# air.net
KiCad netlist of a schematic drawn in EAGLE
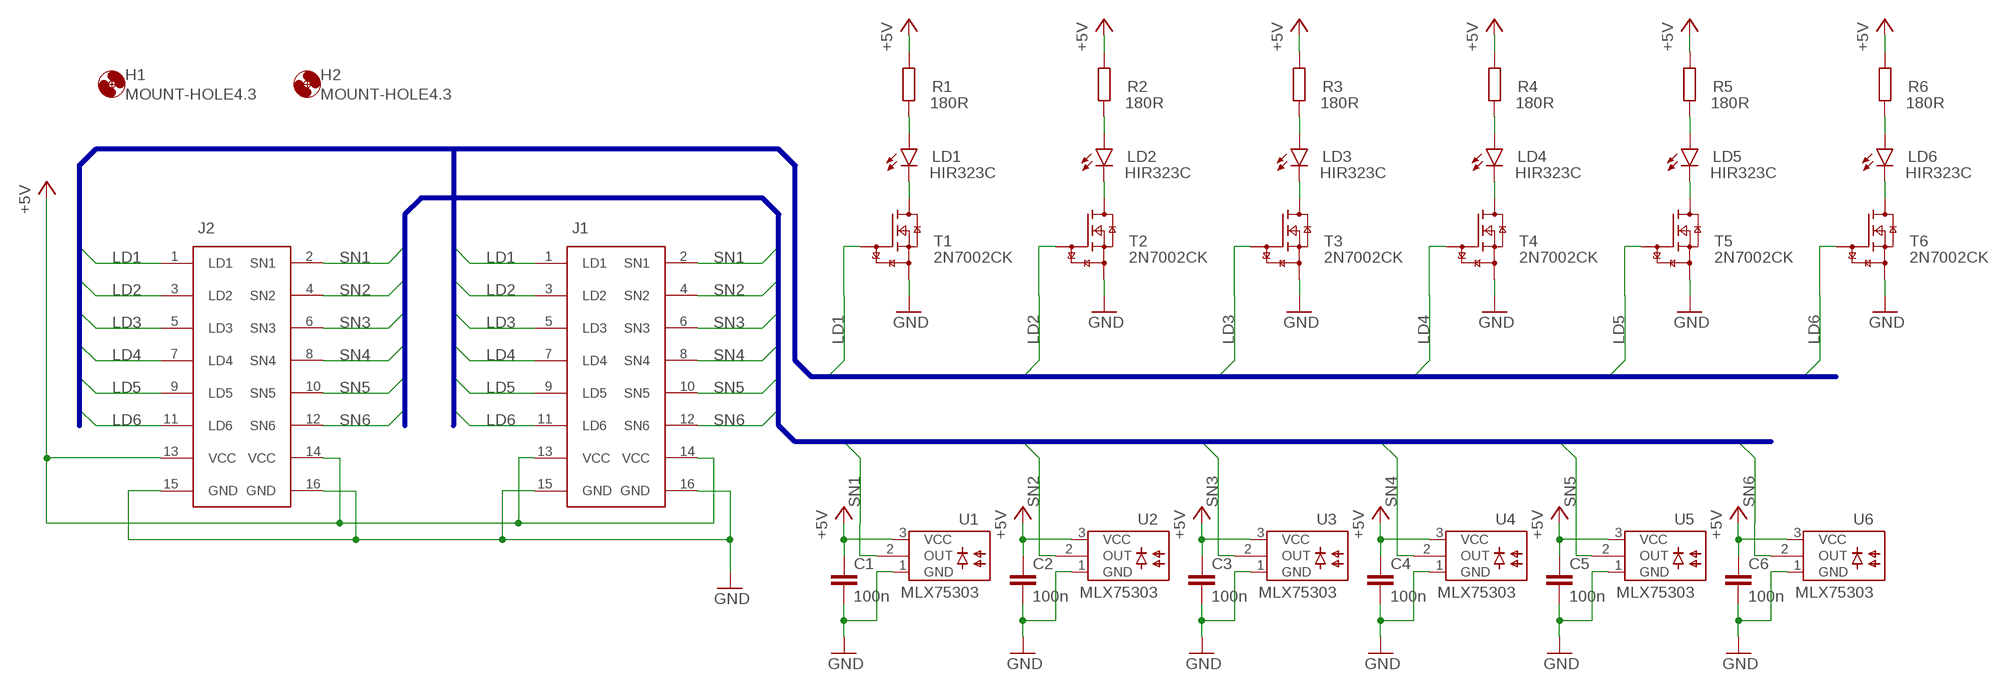
[diagram p0: schematic, sheet 1]

(export (version "E")
  (design (tool "Eeschema 10.0.6"))
  (components
    (comp (ref "C1")
      (value "100n")
      (footprint "eagle-import:C0805K")
      (libsource (lib "eagle-import") (part "C-EUC0805K"))
    )
    (comp (ref "C2")
      (value "100n")
      (footprint "eagle-import:C0805K")
      (libsource (lib "eagle-import") (part "C-EUC0805K"))
    )
    (comp (ref "C3")
      (value "100n")
      (footprint "eagle-import:C0805K")
      (libsource (lib "eagle-import") (part "C-EUC0805K"))
    )
    (comp (ref "C4")
      (value "100n")
      (footprint "eagle-import:C0805K")
      (libsource (lib "eagle-import") (part "C-EUC0805K"))
    )
    (comp (ref "C5")
      (value "100n")
      (footprint "eagle-import:C0805K")
      (libsource (lib "eagle-import") (part "C-EUC0805K"))
    )
    (comp (ref "C6")
      (value "100n")
      (footprint "eagle-import:C0805K")
      (libsource (lib "eagle-import") (part "C-EUC0805K"))
    )
    (comp (ref "H1")
      (value "MOUNT-HOLE4.3")
      (footprint "eagle-import:4,3")
      (libsource (lib "eagle-import") (part "MOUNT-HOLE4.3"))
    )
    (comp (ref "H2")
      (value "MOUNT-HOLE4.3")
      (footprint "eagle-import:4,3")
      (libsource (lib "eagle-import") (part "MOUNT-HOLE4.3"))
    )
    (comp (ref "J1")
      (value "2516-SMD-AIR")
      (footprint "eagle-import:612X1620621")
      (libsource (lib "eagle-import") (part "2516-SMD-AIR"))
    )
    (comp (ref "J2")
      (value "2516-SMD-AIR")
      (footprint "eagle-import:612X1620621")
      (libsource (lib "eagle-import") (part "2516-SMD-AIR"))
    )
    (comp (ref "LD1")
      (value "HIR323C")
      (footprint "eagle-import:LEDRD254W60D590H600B")
      (libsource (lib "eagle-import") (part "HIR323C"))
    )
    (comp (ref "LD2")
      (value "HIR323C")
      (footprint "eagle-import:LEDRD254W60D590H600B")
      (libsource (lib "eagle-import") (part "HIR323C"))
    )
    (comp (ref "LD3")
      (value "HIR323C")
      (footprint "eagle-import:LEDRD254W60D590H600B")
      (libsource (lib "eagle-import") (part "HIR323C"))
    )
    (comp (ref "LD4")
      (value "HIR323C")
      (footprint "eagle-import:LEDRD254W60D590H600B")
      (libsource (lib "eagle-import") (part "HIR323C"))
    )
    (comp (ref "LD5")
      (value "HIR323C")
      (footprint "eagle-import:LEDRD254W60D590H600B")
      (libsource (lib "eagle-import") (part "HIR323C"))
    )
    (comp (ref "LD6")
      (value "HIR323C")
      (footprint "eagle-import:LEDRD254W60D590H600B")
      (libsource (lib "eagle-import") (part "HIR323C"))
    )
    (comp (ref "R1")
      (value "180R")
      (footprint "eagle-import:R0805")
      (libsource (lib "eagle-import") (part "R-EU_R0805"))
    )
    (comp (ref "R2")
      (value "180R")
      (footprint "eagle-import:R0805")
      (libsource (lib "eagle-import") (part "R-EU_R0805"))
    )
    (comp (ref "R3")
      (value "180R")
      (footprint "eagle-import:R0805")
      (libsource (lib "eagle-import") (part "R-EU_R0805"))
    )
    (comp (ref "R4")
      (value "180R")
      (footprint "eagle-import:R0805")
      (libsource (lib "eagle-import") (part "R-EU_R0805"))
    )
    (comp (ref "R5")
      (value "180R")
      (footprint "eagle-import:R0805")
      (libsource (lib "eagle-import") (part "R-EU_R0805"))
    )
    (comp (ref "R6")
      (value "180R")
      (footprint "eagle-import:R0805")
      (libsource (lib "eagle-import") (part "R-EU_R0805"))
    )
    (comp (ref "T1")
      (value "2N7002CK")
      (footprint "eagle-import:SOT23")
      (libsource (lib "eagle-import") (part "2N7002CK"))
    )
    (comp (ref "T2")
      (value "2N7002CK")
      (footprint "eagle-import:SOT23")
      (libsource (lib "eagle-import") (part "2N7002CK"))
    )
    (comp (ref "T3")
      (value "2N7002CK")
      (footprint "eagle-import:SOT23")
      (libsource (lib "eagle-import") (part "2N7002CK"))
    )
    (comp (ref "T4")
      (value "2N7002CK")
      (footprint "eagle-import:SOT23")
      (libsource (lib "eagle-import") (part "2N7002CK"))
    )
    (comp (ref "T5")
      (value "2N7002CK")
      (footprint "eagle-import:SOT23")
      (libsource (lib "eagle-import") (part "2N7002CK"))
    )
    (comp (ref "T6")
      (value "2N7002CK")
      (footprint "eagle-import:SOT23")
      (libsource (lib "eagle-import") (part "2N7002CK"))
    )
    (comp (ref "U1")
      (value "MLX75303")
      (footprint "eagle-import:SOIC127P600X147-8N")
      (libsource (lib "eagle-import") (part "MLX75303"))
    )
    (comp (ref "U2")
      (value "MLX75303")
      (footprint "eagle-import:SOIC127P600X147-8N")
      (libsource (lib "eagle-import") (part "MLX75303"))
    )
    (comp (ref "U3")
      (value "MLX75303")
      (footprint "eagle-import:SOIC127P600X147-8N")
      (libsource (lib "eagle-import") (part "MLX75303"))
    )
    (comp (ref "U4")
      (value "MLX75303")
      (footprint "eagle-import:SOIC127P600X147-8N")
      (libsource (lib "eagle-import") (part "MLX75303"))
    )
    (comp (ref "U5")
      (value "MLX75303")
      (footprint "eagle-import:SOIC127P600X147-8N")
      (libsource (lib "eagle-import") (part "MLX75303"))
    )
    (comp (ref "U6")
      (value "MLX75303")
      (footprint "eagle-import:SOIC127P600X147-8N")
      (libsource (lib "eagle-import") (part "MLX75303"))
    )
  )
  (nets
    (net (code "1") (name "+5V") (class "Default")
      (node (ref "C1") (pin "1") (pinfunction "1_1") (pintype "passive"))
      (node (ref "C2") (pin "1") (pinfunction "1_1") (pintype "passive"))
      (node (ref "C3") (pin "1") (pinfunction "1_1") (pintype "passive"))
      (node (ref "C4") (pin "1") (pinfunction "1_1") (pintype "passive"))
      (node (ref "C5") (pin "1") (pinfunction "1_1") (pintype "passive"))
      (node (ref "C6") (pin "1") (pinfunction "1_1") (pintype "passive"))
      (node (ref "J1") (pin "13") (pinfunction "VCC_13") (pintype "passive"))
      (node (ref "J1") (pin "14") (pinfunction "VCC_14") (pintype "passive"))
      (node (ref "J2") (pin "13") (pinfunction "VCC_13") (pintype "passive"))
      (node (ref "J2") (pin "14") (pinfunction "VCC_14") (pintype "passive"))
      (node (ref "R1") (pin "2") (pinfunction "2_2") (pintype "passive"))
      (node (ref "R2") (pin "2") (pinfunction "2_2") (pintype "passive"))
      (node (ref "R3") (pin "2") (pinfunction "2_2") (pintype "passive"))
      (node (ref "R4") (pin "2") (pinfunction "2_2") (pintype "passive"))
      (node (ref "R5") (pin "2") (pinfunction "2_2") (pintype "passive"))
      (node (ref "R6") (pin "2") (pinfunction "2_2") (pintype "passive"))
      (node (ref "U1") (pin "3") (pinfunction "VCC_3") (pintype "power_in"))
      (node (ref "U2") (pin "3") (pinfunction "VCC_3") (pintype "power_in"))
      (node (ref "U3") (pin "3") (pinfunction "VCC_3") (pintype "power_in"))
      (node (ref "U4") (pin "3") (pinfunction "VCC_3") (pintype "power_in"))
      (node (ref "U5") (pin "3") (pinfunction "VCC_3") (pintype "power_in"))
      (node (ref "U6") (pin "3") (pinfunction "VCC_3") (pintype "power_in"))
    )
    (net (code "2") (name "/LD1") (class "Default")
      (node (ref "J1") (pin "1") (pinfunction "LD1_1") (pintype "passive"))
      (node (ref "J2") (pin "1") (pinfunction "LD1_1") (pintype "passive"))
      (node (ref "T1") (pin "1") (pinfunction "G_1") (pintype "passive"))
    )
    (net (code "3") (name "/LD2") (class "Default")
      (node (ref "J1") (pin "3") (pinfunction "LD2_3") (pintype "passive"))
      (node (ref "J2") (pin "3") (pinfunction "LD2_3") (pintype "passive"))
      (node (ref "T2") (pin "1") (pinfunction "G_1") (pintype "passive"))
    )
    (net (code "4") (name "/LD3") (class "Default")
      (node (ref "J1") (pin "5") (pinfunction "LD3_5") (pintype "passive"))
      (node (ref "J2") (pin "5") (pinfunction "LD3_5") (pintype "passive"))
      (node (ref "T3") (pin "1") (pinfunction "G_1") (pintype "passive"))
    )
    (net (code "5") (name "/LD4") (class "Default")
      (node (ref "J1") (pin "7") (pinfunction "LD4_7") (pintype "passive"))
      (node (ref "J2") (pin "7") (pinfunction "LD4_7") (pintype "passive"))
      (node (ref "T4") (pin "1") (pinfunction "G_1") (pintype "passive"))
    )
    (net (code "6") (name "/LD5") (class "Default")
      (node (ref "J1") (pin "9") (pinfunction "LD5_9") (pintype "passive"))
      (node (ref "J2") (pin "9") (pinfunction "LD5_9") (pintype "passive"))
      (node (ref "T5") (pin "1") (pinfunction "G_1") (pintype "passive"))
    )
    (net (code "7") (name "/LD6") (class "Default")
      (node (ref "J1") (pin "11") (pinfunction "LD6_11") (pintype "passive"))
      (node (ref "J2") (pin "11") (pinfunction "LD6_11") (pintype "passive"))
      (node (ref "T6") (pin "1") (pinfunction "G_1") (pintype "passive"))
    )
    (net (code "8") (name "/SN1") (class "Default")
      (node (ref "J1") (pin "2") (pinfunction "SN1_2") (pintype "passive"))
      (node (ref "J2") (pin "2") (pinfunction "SN1_2") (pintype "passive"))
      (node (ref "U1") (pin "2") (pinfunction "OUT_2") (pintype "output"))
    )
    (net (code "9") (name "/SN2") (class "Default")
      (node (ref "J1") (pin "4") (pinfunction "SN2_4") (pintype "passive"))
      (node (ref "J2") (pin "4") (pinfunction "SN2_4") (pintype "passive"))
      (node (ref "U2") (pin "2") (pinfunction "OUT_2") (pintype "output"))
    )
    (net (code "10") (name "/SN3") (class "Default")
      (node (ref "J1") (pin "6") (pinfunction "SN3_6") (pintype "passive"))
      (node (ref "J2") (pin "6") (pinfunction "SN3_6") (pintype "passive"))
      (node (ref "U3") (pin "2") (pinfunction "OUT_2") (pintype "output"))
    )
    (net (code "11") (name "/SN4") (class "Default")
      (node (ref "J1") (pin "8") (pinfunction "SN4_8") (pintype "passive"))
      (node (ref "J2") (pin "8") (pinfunction "SN4_8") (pintype "passive"))
      (node (ref "U4") (pin "2") (pinfunction "OUT_2") (pintype "output"))
    )
    (net (code "12") (name "/SN5") (class "Default")
      (node (ref "J1") (pin "10") (pinfunction "SN5_10") (pintype "passive"))
      (node (ref "J2") (pin "10") (pinfunction "SN5_10") (pintype "passive"))
      (node (ref "U5") (pin "2") (pinfunction "OUT_2") (pintype "output"))
    )
    (net (code "13") (name "/SN6") (class "Default")
      (node (ref "J1") (pin "12") (pinfunction "SN6_12") (pintype "passive"))
      (node (ref "J2") (pin "12") (pinfunction "SN6_12") (pintype "passive"))
      (node (ref "U6") (pin "2") (pinfunction "OUT_2") (pintype "output"))
    )
    (net (code "14") (name "GND") (class "Default")
      (node (ref "C1") (pin "2") (pinfunction "2_2") (pintype "passive"))
      (node (ref "C2") (pin "2") (pinfunction "2_2") (pintype "passive"))
      (node (ref "C3") (pin "2") (pinfunction "2_2") (pintype "passive"))
      (node (ref "C4") (pin "2") (pinfunction "2_2") (pintype "passive"))
      (node (ref "C5") (pin "2") (pinfunction "2_2") (pintype "passive"))
      (node (ref "C6") (pin "2") (pinfunction "2_2") (pintype "passive"))
      (node (ref "J1") (pin "15") (pinfunction "GND_15") (pintype "passive"))
      (node (ref "J1") (pin "16") (pinfunction "GND_16") (pintype "passive"))
      (node (ref "J2") (pin "15") (pinfunction "GND_15") (pintype "passive"))
      (node (ref "J2") (pin "16") (pinfunction "GND_16") (pintype "passive"))
      (node (ref "T1") (pin "2") (pinfunction "S_2") (pintype "passive"))
      (node (ref "T2") (pin "2") (pinfunction "S_2") (pintype "passive"))
      (node (ref "T3") (pin "2") (pinfunction "S_2") (pintype "passive"))
      (node (ref "T4") (pin "2") (pinfunction "S_2") (pintype "passive"))
      (node (ref "T5") (pin "2") (pinfunction "S_2") (pintype "passive"))
      (node (ref "T6") (pin "2") (pinfunction "S_2") (pintype "passive"))
      (node (ref "U1") (pin "1") (pinfunction "GND_1") (pintype "power_in"))
      (node (ref "U2") (pin "1") (pinfunction "GND_1") (pintype "power_in"))
      (node (ref "U3") (pin "1") (pinfunction "GND_1") (pintype "power_in"))
      (node (ref "U4") (pin "1") (pinfunction "GND_1") (pintype "power_in"))
      (node (ref "U5") (pin "1") (pinfunction "GND_1") (pintype "power_in"))
      (node (ref "U6") (pin "1") (pinfunction "GND_1") (pintype "power_in"))
    )
    (net (code "15") (name "Net-(LD1-A)") (class "Default")
      (node (ref "LD1") (pin "1") (pinfunction "A_1") (pintype "passive"))
      (node (ref "R1") (pin "1") (pinfunction "1_1") (pintype "passive"))
    )
    (net (code "16") (name "Net-(LD1-C)") (class "Default")
      (node (ref "LD1") (pin "2") (pinfunction "C_2") (pintype "passive"))
      (node (ref "T1") (pin "3") (pinfunction "D_3") (pintype "passive"))
    )
    (net (code "17") (name "Net-(LD2-A)") (class "Default")
      (node (ref "LD2") (pin "1") (pinfunction "A_1") (pintype "passive"))
      (node (ref "R2") (pin "1") (pinfunction "1_1") (pintype "passive"))
    )
    (net (code "18") (name "Net-(LD2-C)") (class "Default")
      (node (ref "LD2") (pin "2") (pinfunction "C_2") (pintype "passive"))
      (node (ref "T2") (pin "3") (pinfunction "D_3") (pintype "passive"))
    )
    (net (code "19") (name "Net-(LD3-A)") (class "Default")
      (node (ref "LD3") (pin "1") (pinfunction "A_1") (pintype "passive"))
      (node (ref "R3") (pin "1") (pinfunction "1_1") (pintype "passive"))
    )
    (net (code "20") (name "Net-(LD3-C)") (class "Default")
      (node (ref "LD3") (pin "2") (pinfunction "C_2") (pintype "passive"))
      (node (ref "T3") (pin "3") (pinfunction "D_3") (pintype "passive"))
    )
    (net (code "21") (name "Net-(LD4-A)") (class "Default")
      (node (ref "LD4") (pin "1") (pinfunction "A_1") (pintype "passive"))
      (node (ref "R4") (pin "1") (pinfunction "1_1") (pintype "passive"))
    )
    (net (code "22") (name "Net-(LD4-C)") (class "Default")
      (node (ref "LD4") (pin "2") (pinfunction "C_2") (pintype "passive"))
      (node (ref "T4") (pin "3") (pinfunction "D_3") (pintype "passive"))
    )
    (net (code "23") (name "Net-(LD5-A)") (class "Default")
      (node (ref "LD5") (pin "1") (pinfunction "A_1") (pintype "passive"))
      (node (ref "R5") (pin "1") (pinfunction "1_1") (pintype "passive"))
    )
    (net (code "24") (name "Net-(LD5-C)") (class "Default")
      (node (ref "LD5") (pin "2") (pinfunction "C_2") (pintype "passive"))
      (node (ref "T5") (pin "3") (pinfunction "D_3") (pintype "passive"))
    )
    (net (code "25") (name "Net-(LD6-A)") (class "Default")
      (node (ref "LD6") (pin "1") (pinfunction "A_1") (pintype "passive"))
      (node (ref "R6") (pin "1") (pinfunction "1_1") (pintype "passive"))
    )
    (net (code "26") (name "Net-(LD6-C)") (class "Default")
      (node (ref "LD6") (pin "2") (pinfunction "C_2") (pintype "passive"))
      (node (ref "T6") (pin "3") (pinfunction "D_3") (pintype "passive"))
    )
  )
)
